# 1_fakewire.net
KiCad netlist of a schematic drawn in Altium Designer
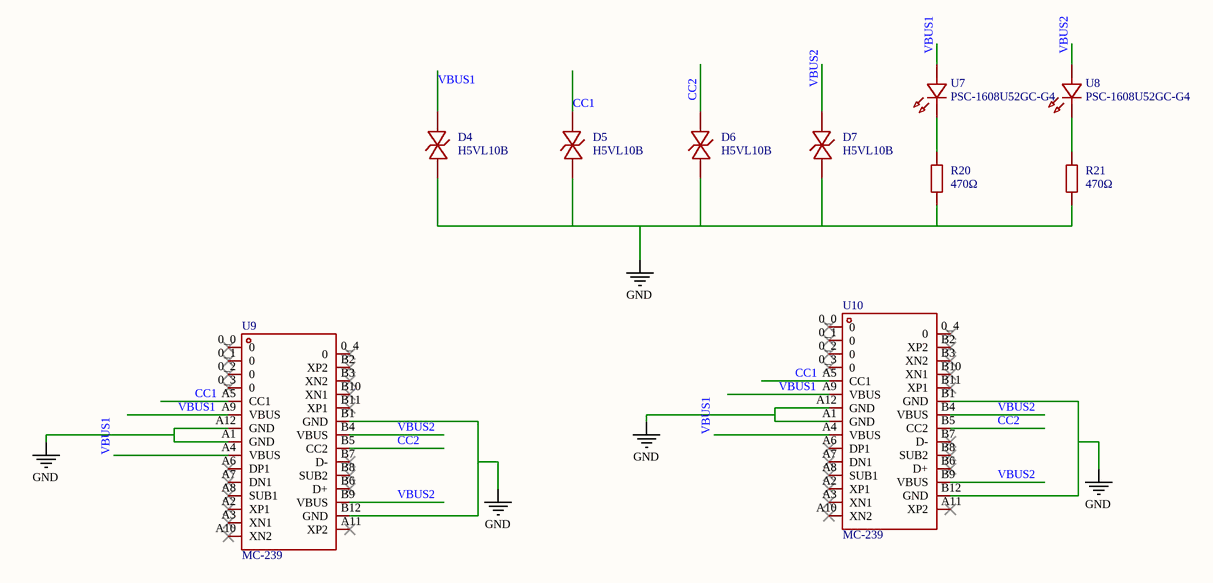
[diagram p0: 1_fakewire.schdoc]

(export (version "E")
  (design (tool "Eeschema 10.0.6"))
  (components
    (comp (ref "D4")
      (value "H5VL10B")
      (footprint "SOD-882_L1.0-W0.6-BI")
      (fields (field (name "MANUFACTURER") "宏迦橙"))
      (libsource (lib "altium-import") (part "root_1_H5VL10B_"))
    )
    (comp (ref "D5")
      (value "H5VL10B")
      (footprint "SOD-882_L1.0-W0.6-BI")
      (fields (field (name "MANUFACTURER") "宏迦橙"))
      (libsource (lib "altium-import") (part "root_1_H5VL10B_"))
    )
    (comp (ref "D6")
      (value "H5VL10B")
      (footprint "SOD-882_L1.0-W0.6-BI")
      (fields (field (name "MANUFACTURER") "宏迦橙"))
      (libsource (lib "altium-import") (part "root_1_H5VL10B_"))
    )
    (comp (ref "D7")
      (value "H5VL10B")
      (footprint "SOD-882_L1.0-W0.6-BI")
      (fields (field (name "MANUFACTURER") "宏迦橙"))
      (libsource (lib "altium-import") (part "root_1_H5VL10B_"))
    )
    (comp (ref "R20")
      (value "470Ω")
      (footprint "R0603")
      (fields
        (field (name "MANUFACTURER") "YAGEO(国巨)")
        (field (name "MANUFACTURER PART") "RC0603FR-07470RL")
        (field (name "TOLERANCE") "±1%")
      )
      (libsource (lib "altium-import") (part "root_1_RC0603FR-07470RL_"))
    )
    (comp (ref "R21")
      (value "470Ω")
      (footprint "R0603")
      (fields
        (field (name "MANUFACTURER") "YAGEO(国巨)")
        (field (name "MANUFACTURER PART") "RC0603FR-07470RL")
        (field (name "TOLERANCE") "±1%")
      )
      (libsource (lib "altium-import") (part "root_1_RC0603FR-07470RL_"))
    )
    (comp (ref "U7")
      (value "PSC-1608U52GC-G4")
      (footprint "LED0603-RD_GREEN")
      (fields (field (name "MANUFACTURER") "HONGLITRONIC(鸿利光电)"))
      (libsource (lib "altium-import") (part "root_1_PSC-1608U52GC-G4_"))
    )
    (comp (ref "U8")
      (value "PSC-1608U52GC-G4")
      (footprint "LED0603-RD_GREEN")
      (fields (field (name "MANUFACTURER") "HONGLITRONIC(鸿利光电)"))
      (libsource (lib "altium-import") (part "root_1_PSC-1608U52GC-G4_"))
    )
    (comp (ref "U9")
      (value "MC-239")
      (footprint "CONN-TH_MC-239")
      (fields (field (name "MANUFACTURER") "HANBO(汉博)"))
      (libsource (lib "altium-import") (part "root_0_MC-239_"))
    )
    (comp (ref "U10")
      (value "MC-239")
      (footprint "CONN-TH_MC-239")
      (fields (field (name "MANUFACTURER") "HANBO(汉博)"))
      (libsource (lib "altium-import") (part "root_0_MC-239_"))
    )
  )
  (nets
    (net (code "1") (name "/CC1") (class "Default")
      (node (ref "D5") (pin "2") (pinfunction "A_2") (pintype "passive"))
      (node (ref "U10") (pin "A5") (pinfunction "CC1_A5") (pintype "passive"))
      (node (ref "U9") (pin "A5") (pinfunction "CC1_A5") (pintype "passive"))
    )
    (net (code "2") (name "/CC2") (class "Default")
      (node (ref "D6") (pin "2") (pinfunction "A_2") (pintype "passive"))
      (node (ref "U10") (pin "B5") (pinfunction "CC2_B5") (pintype "passive"))
      (node (ref "U9") (pin "B5") (pinfunction "CC2_B5") (pintype "passive"))
    )
    (net (code "3") (name "/VBUS1") (class "Default")
      (node (ref "D4") (pin "2") (pinfunction "A_2") (pintype "passive"))
      (node (ref "U10") (pin "A4") (pinfunction "VBUS_A4") (pintype "passive"))
      (node (ref "U10") (pin "A9") (pinfunction "VBUS_A9") (pintype "passive"))
      (node (ref "U7") (pin "2") (pinfunction "A_2") (pintype "passive"))
      (node (ref "U9") (pin "A4") (pinfunction "VBUS_A4") (pintype "passive"))
      (node (ref "U9") (pin "A9") (pinfunction "VBUS_A9") (pintype "passive"))
    )
    (net (code "4") (name "/VBUS2") (class "Default")
      (node (ref "D7") (pin "2") (pinfunction "A_2") (pintype "passive"))
      (node (ref "U10") (pin "B4") (pinfunction "VBUS_B4") (pintype "passive"))
      (node (ref "U10") (pin "B9") (pinfunction "VBUS_B9") (pintype "passive"))
      (node (ref "U8") (pin "2") (pinfunction "A_2") (pintype "passive"))
      (node (ref "U9") (pin "B4") (pinfunction "VBUS_B4") (pintype "passive"))
      (node (ref "U9") (pin "B9") (pinfunction "VBUS_B9") (pintype "passive"))
    )
    (net (code "5") (name "GND") (class "Default")
      (node (ref "D4") (pin "1") (pinfunction "C_1") (pintype "passive"))
      (node (ref "D5") (pin "1") (pinfunction "C_1") (pintype "passive"))
      (node (ref "D6") (pin "1") (pinfunction "C_1") (pintype "passive"))
      (node (ref "D7") (pin "1") (pinfunction "C_1") (pintype "passive"))
      (node (ref "R20") (pin "1") (pinfunction "1_1") (pintype "passive"))
      (node (ref "R21") (pin "1") (pinfunction "1_1") (pintype "passive"))
      (node (ref "U10") (pin "A1") (pinfunction "GND_A1") (pintype "passive"))
      (node (ref "U10") (pin "A12") (pinfunction "GND_A12") (pintype "passive"))
      (node (ref "U10") (pin "B1") (pinfunction "GND_B1") (pintype "passive"))
      (node (ref "U10") (pin "B12") (pinfunction "GND_B12") (pintype "passive"))
      (node (ref "U9") (pin "A1") (pinfunction "GND_A1") (pintype "passive"))
      (node (ref "U9") (pin "A12") (pinfunction "GND_A12") (pintype "passive"))
      (node (ref "U9") (pin "B1") (pinfunction "GND_B1") (pintype "passive"))
      (node (ref "U9") (pin "B12") (pinfunction "GND_B12") (pintype "passive"))
    )
    (net (code "6") (name "Net-(U7-K)") (class "Default")
      (node (ref "R20") (pin "2") (pinfunction "2_2") (pintype "passive"))
      (node (ref "U7") (pin "1") (pinfunction "K_1") (pintype "passive"))
    )
    (net (code "7") (name "Net-(U8-K)") (class "Default")
      (node (ref "R21") (pin "2") (pinfunction "2_2") (pintype "passive"))
      (node (ref "U8") (pin "1") (pinfunction "K_1") (pintype "passive"))
    )
    (net (code "8") (name "unconnected-(U9-0-Pad0_0)") (class "Default")
      (node (ref "U9") (pin "0_0") (pinfunction "0_0_0") (pintype "passive+no_connect"))
    )
    (net (code "9") (name "unconnected-(U9-0-Pad0_1)") (class "Default")
      (node (ref "U9") (pin "0_1") (pinfunction "0_0_1") (pintype "passive+no_connect"))
    )
    (net (code "10") (name "unconnected-(U9-0-Pad0_2)") (class "Default")
      (node (ref "U9") (pin "0_2") (pinfunction "0_0_2") (pintype "passive+no_connect"))
    )
    (net (code "11") (name "unconnected-(U9-0-Pad0_3)") (class "Default")
      (node (ref "U9") (pin "0_3") (pinfunction "0_0_3") (pintype "passive+no_connect"))
    )
    (net (code "12") (name "unconnected-(U9-0-Pad0_4)") (class "Default")
      (node (ref "U9") (pin "0_4") (pinfunction "0_0_4") (pintype "passive+no_connect"))
    )
    (net (code "13") (name "unconnected-(U9-D+-PadB6)") (class "Default")
      (node (ref "U9") (pin "B6") (pinfunction "D+_B6") (pintype "passive+no_connect"))
    )
    (net (code "14") (name "unconnected-(U9-D--PadB7)") (class "Default")
      (node (ref "U9") (pin "B7") (pinfunction "D-_B7") (pintype "passive+no_connect"))
    )
    (net (code "15") (name "unconnected-(U9-DN1-PadA7)") (class "Default")
      (node (ref "U9") (pin "A7") (pinfunction "DN1_A7") (pintype "passive+no_connect"))
    )
    (net (code "16") (name "unconnected-(U9-DP1-PadA6)") (class "Default")
      (node (ref "U9") (pin "A6") (pinfunction "DP1_A6") (pintype "passive+no_connect"))
    )
    (net (code "17") (name "unconnected-(U9-SUB1-PadA8)") (class "Default")
      (node (ref "U9") (pin "A8") (pinfunction "SUB1_A8") (pintype "passive+no_connect"))
    )
    (net (code "18") (name "unconnected-(U9-SUB2-PadB8)") (class "Default")
      (node (ref "U9") (pin "B8") (pinfunction "SUB2_B8") (pintype "passive+no_connect"))
    )
    (net (code "19") (name "unconnected-(U9-XN1-PadA3)") (class "Default")
      (node (ref "U9") (pin "A3") (pinfunction "XN1_A3") (pintype "passive+no_connect"))
    )
    (net (code "20") (name "unconnected-(U9-XN1-PadB10)") (class "Default")
      (node (ref "U9") (pin "B10") (pinfunction "XN1_B10") (pintype "passive+no_connect"))
    )
    (net (code "21") (name "unconnected-(U9-XN2-PadA10)") (class "Default")
      (node (ref "U9") (pin "A10") (pinfunction "XN2_A10") (pintype "passive+no_connect"))
    )
    (net (code "22") (name "unconnected-(U9-XN2-PadB3)") (class "Default")
      (node (ref "U9") (pin "B3") (pinfunction "XN2_B3") (pintype "passive+no_connect"))
    )
    (net (code "23") (name "unconnected-(U9-XP1-PadA2)") (class "Default")
      (node (ref "U9") (pin "A2") (pinfunction "XP1_A2") (pintype "passive+no_connect"))
    )
    (net (code "24") (name "unconnected-(U9-XP1-PadB11)") (class "Default")
      (node (ref "U9") (pin "B11") (pinfunction "XP1_B11") (pintype "passive+no_connect"))
    )
    (net (code "25") (name "unconnected-(U9-XP2-PadA11)") (class "Default")
      (node (ref "U9") (pin "A11") (pinfunction "XP2_A11") (pintype "passive+no_connect"))
    )
    (net (code "26") (name "unconnected-(U9-XP2-PadB2)") (class "Default")
      (node (ref "U9") (pin "B2") (pinfunction "XP2_B2") (pintype "passive+no_connect"))
    )
    (net (code "27") (name "unconnected-(U10-0-Pad0_0)") (class "Default")
      (node (ref "U10") (pin "0_0") (pinfunction "0_0_0") (pintype "passive+no_connect"))
    )
    (net (code "28") (name "unconnected-(U10-0-Pad0_1)") (class "Default")
      (node (ref "U10") (pin "0_1") (pinfunction "0_0_1") (pintype "passive+no_connect"))
    )
    (net (code "29") (name "unconnected-(U10-0-Pad0_2)") (class "Default")
      (node (ref "U10") (pin "0_2") (pinfunction "0_0_2") (pintype "passive+no_connect"))
    )
    (net (code "30") (name "unconnected-(U10-0-Pad0_3)") (class "Default")
      (node (ref "U10") (pin "0_3") (pinfunction "0_0_3") (pintype "passive+no_connect"))
    )
    (net (code "31") (name "unconnected-(U10-0-Pad0_4)") (class "Default")
      (node (ref "U10") (pin "0_4") (pinfunction "0_0_4") (pintype "passive+no_connect"))
    )
    (net (code "32") (name "unconnected-(U10-D+-PadB6)") (class "Default")
      (node (ref "U10") (pin "B6") (pinfunction "D+_B6") (pintype "passive+no_connect"))
    )
    (net (code "33") (name "unconnected-(U10-D--PadB7)") (class "Default")
      (node (ref "U10") (pin "B7") (pinfunction "D-_B7") (pintype "passive+no_connect"))
    )
    (net (code "34") (name "unconnected-(U10-DN1-PadA7)") (class "Default")
      (node (ref "U10") (pin "A7") (pinfunction "DN1_A7") (pintype "passive+no_connect"))
    )
    (net (code "35") (name "unconnected-(U10-DP1-PadA6)") (class "Default")
      (node (ref "U10") (pin "A6") (pinfunction "DP1_A6") (pintype "passive+no_connect"))
    )
    (net (code "36") (name "unconnected-(U10-SUB1-PadA8)") (class "Default")
      (node (ref "U10") (pin "A8") (pinfunction "SUB1_A8") (pintype "passive+no_connect"))
    )
    (net (code "37") (name "unconnected-(U10-SUB2-PadB8)") (class "Default")
      (node (ref "U10") (pin "B8") (pinfunction "SUB2_B8") (pintype "passive+no_connect"))
    )
    (net (code "38") (name "unconnected-(U10-XN1-PadA3)") (class "Default")
      (node (ref "U10") (pin "A3") (pinfunction "XN1_A3") (pintype "passive+no_connect"))
    )
    (net (code "39") (name "unconnected-(U10-XN1-PadB10)") (class "Default")
      (node (ref "U10") (pin "B10") (pinfunction "XN1_B10") (pintype "passive+no_connect"))
    )
    (net (code "40") (name "unconnected-(U10-XN2-PadA10)") (class "Default")
      (node (ref "U10") (pin "A10") (pinfunction "XN2_A10") (pintype "passive+no_connect"))
    )
    (net (code "41") (name "unconnected-(U10-XN2-PadB3)") (class "Default")
      (node (ref "U10") (pin "B3") (pinfunction "XN2_B3") (pintype "passive+no_connect"))
    )
    (net (code "42") (name "unconnected-(U10-XP1-PadA2)") (class "Default")
      (node (ref "U10") (pin "A2") (pinfunction "XP1_A2") (pintype "passive+no_connect"))
    )
    (net (code "43") (name "unconnected-(U10-XP1-PadB11)") (class "Default")
      (node (ref "U10") (pin "B11") (pinfunction "XP1_B11") (pintype "passive+no_connect"))
    )
    (net (code "44") (name "unconnected-(U10-XP2-PadA11)") (class "Default")
      (node (ref "U10") (pin "A11") (pinfunction "XP2_A11") (pintype "passive+no_connect"))
    )
    (net (code "45") (name "unconnected-(U10-XP2-PadB2)") (class "Default")
      (node (ref "U10") (pin "B2") (pinfunction "XP2_B2") (pintype "passive+no_connect"))
    )
  )
)
